# I2C_HEADER.net
KiCad netlist of a schematic drawn in Altium Designer
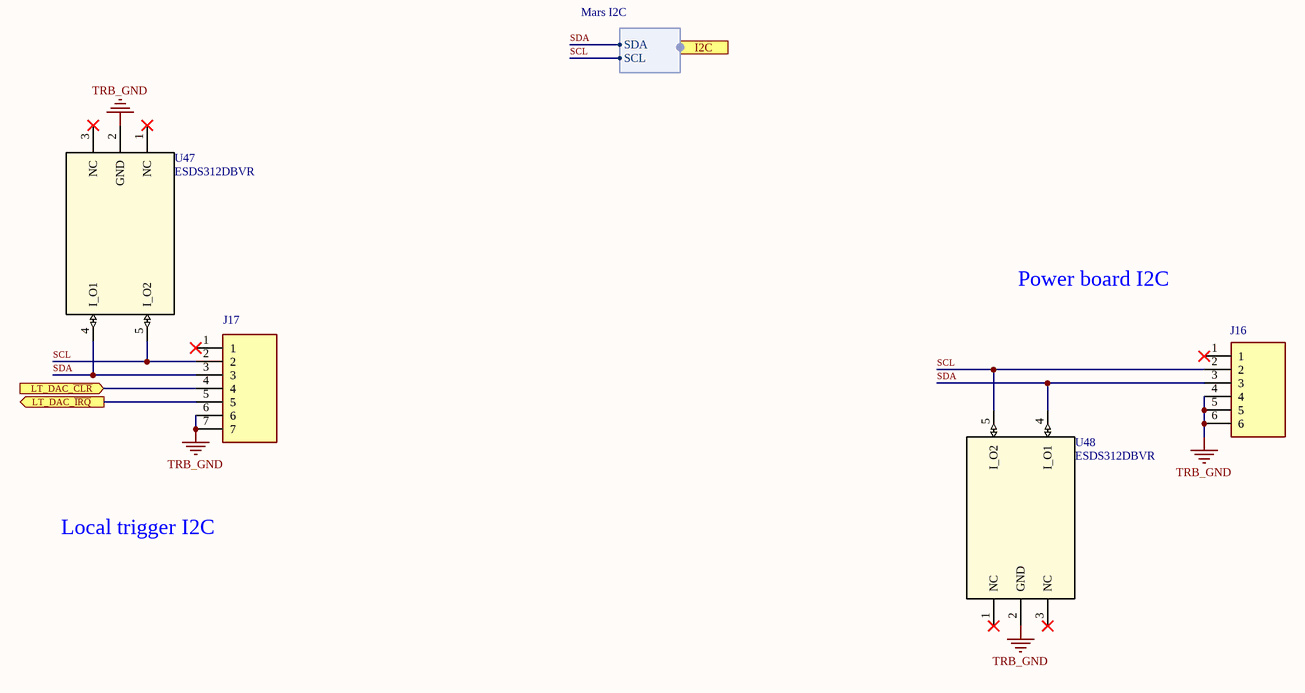
[diagram p0: I2C_HEADER.SchDoc]

(export (version "E")
  (design (tool "Eeschema 10.0.6"))
  (components
    (comp (ref "J16")
      (value "61300611121")
      (footprint "HDRV6W64P0X254_1X6_1524X254X869P")
      (description "Connector")
      (fields (field (name "MOUSER2 PART NUMBER") "710-61300611121"))
      (libsource (lib "Header_Wurth_61300611121_6POS") (part "61300611121"))
    )
    (comp (ref "J17")
      (value "61300711121")
      (footprint "HDRV7W64P0X254_1X7_1778X254X869P")
      (description "Connector")
      (fields (field (name "MOUSER2 PART NUMBER") "710-61300711121"))
      (libsource (lib "Header_Wurth_61300711121_7POS") (part "61300711121"))
    )
    (comp (ref "U47")
      (value "ESDS312DBVR")
      (footprint "DBV0005A_L")
      (description "3.6V Data-Line Surge and 30kV ESD Protection Diode")
      (fields (field (name "MANUFACTURER") "Texas Instruments"))
      (libsource (lib "") (part "ESDS312DBVR_1"))
    )
    (comp (ref "U48")
      (value "ESDS312DBVR")
      (footprint "DBV0005A_L")
      (description "3.6V Data-Line Surge and 30kV ESD Protection Diode")
      (fields (field (name "MANUFACTURER") "Texas Instruments"))
      (libsource (lib "ESDS312DBVR_I2C") (part "ESDS312DBVR"))
    )
  )
  (nets
    (net (code "3") (name "/LT_DAC_~{CLR}") (class "Default")
      (node (ref "J17") (pin "4") (pinfunction "4_4") (pintype "passive"))
    )
    (net (code "4") (name "/LT_DAC_~{IRQ}") (class "Default")
      (node (ref "J17") (pin "5") (pinfunction "5_5") (pintype "passive"))
    )
    (net (code "5") (name "/SCL") (class "Default")
      (node (ref "J16") (pin "2") (pinfunction "2_2") (pintype "passive"))
      (node (ref "J17") (pin "2") (pinfunction "2_2") (pintype "passive"))
      (node (ref "U47") (pin "5") (pinfunction "I_O2_5") (pintype "bidirectional"))
      (node (ref "U48") (pin "5") (pinfunction "I_O2_5") (pintype "bidirectional"))
    )
    (net (code "6") (name "/SDA") (class "Default")
      (node (ref "J16") (pin "3") (pinfunction "3_3") (pintype "passive"))
      (node (ref "J17") (pin "3") (pinfunction "3_3") (pintype "passive"))
      (node (ref "U47") (pin "4") (pinfunction "I_O1_4") (pintype "bidirectional"))
      (node (ref "U48") (pin "4") (pinfunction "I_O1_4") (pintype "bidirectional"))
    )
    (net (code "8") (name "TRB_GND") (class "Default")
      (node (ref "J16") (pin "4") (pinfunction "4_4") (pintype "passive"))
      (node (ref "J16") (pin "5") (pinfunction "5_5") (pintype "passive"))
      (node (ref "J16") (pin "6") (pinfunction "6_6") (pintype "passive"))
      (node (ref "J17") (pin "6") (pinfunction "6_6") (pintype "passive"))
      (node (ref "J17") (pin "7") (pinfunction "7_7") (pintype "passive"))
      (node (ref "U47") (pin "2") (pinfunction "GND_2") (pintype "power_in"))
      (node (ref "U48") (pin "2") (pinfunction "GND_2") (pintype "power_in"))
    )
    (net (code "9") (name "unconnected-(J16-Pad1)") (class "Default")
      (node (ref "J16") (pin "1") (pinfunction "1_1") (pintype "passive+no_connect"))
    )
    (net (code "10") (name "unconnected-(J17-Pad1)") (class "Default")
      (node (ref "J17") (pin "1") (pinfunction "1_1") (pintype "passive+no_connect"))
    )
    (net (code "11") (name "unconnected-(U47-NC-Pad1)") (class "Default")
      (node (ref "U47") (pin "1") (pinfunction "NC_1") (pintype "passive+no_connect"))
    )
    (net (code "12") (name "unconnected-(U47-NC-Pad3)") (class "Default")
      (node (ref "U47") (pin "3") (pinfunction "NC_3") (pintype "passive+no_connect"))
    )
    (net (code "13") (name "unconnected-(U48-NC-Pad1)") (class "Default")
      (node (ref "U48") (pin "1") (pinfunction "NC_1") (pintype "passive+no_connect"))
    )
    (net (code "14") (name "unconnected-(U48-NC-Pad3)") (class "Default")
      (node (ref "U48") (pin "3") (pinfunction "NC_3") (pintype "passive+no_connect"))
    )
  )
)
